# 1_MICROCONTROLADOR.net
KiCad netlist of a schematic drawn in Altium Designer
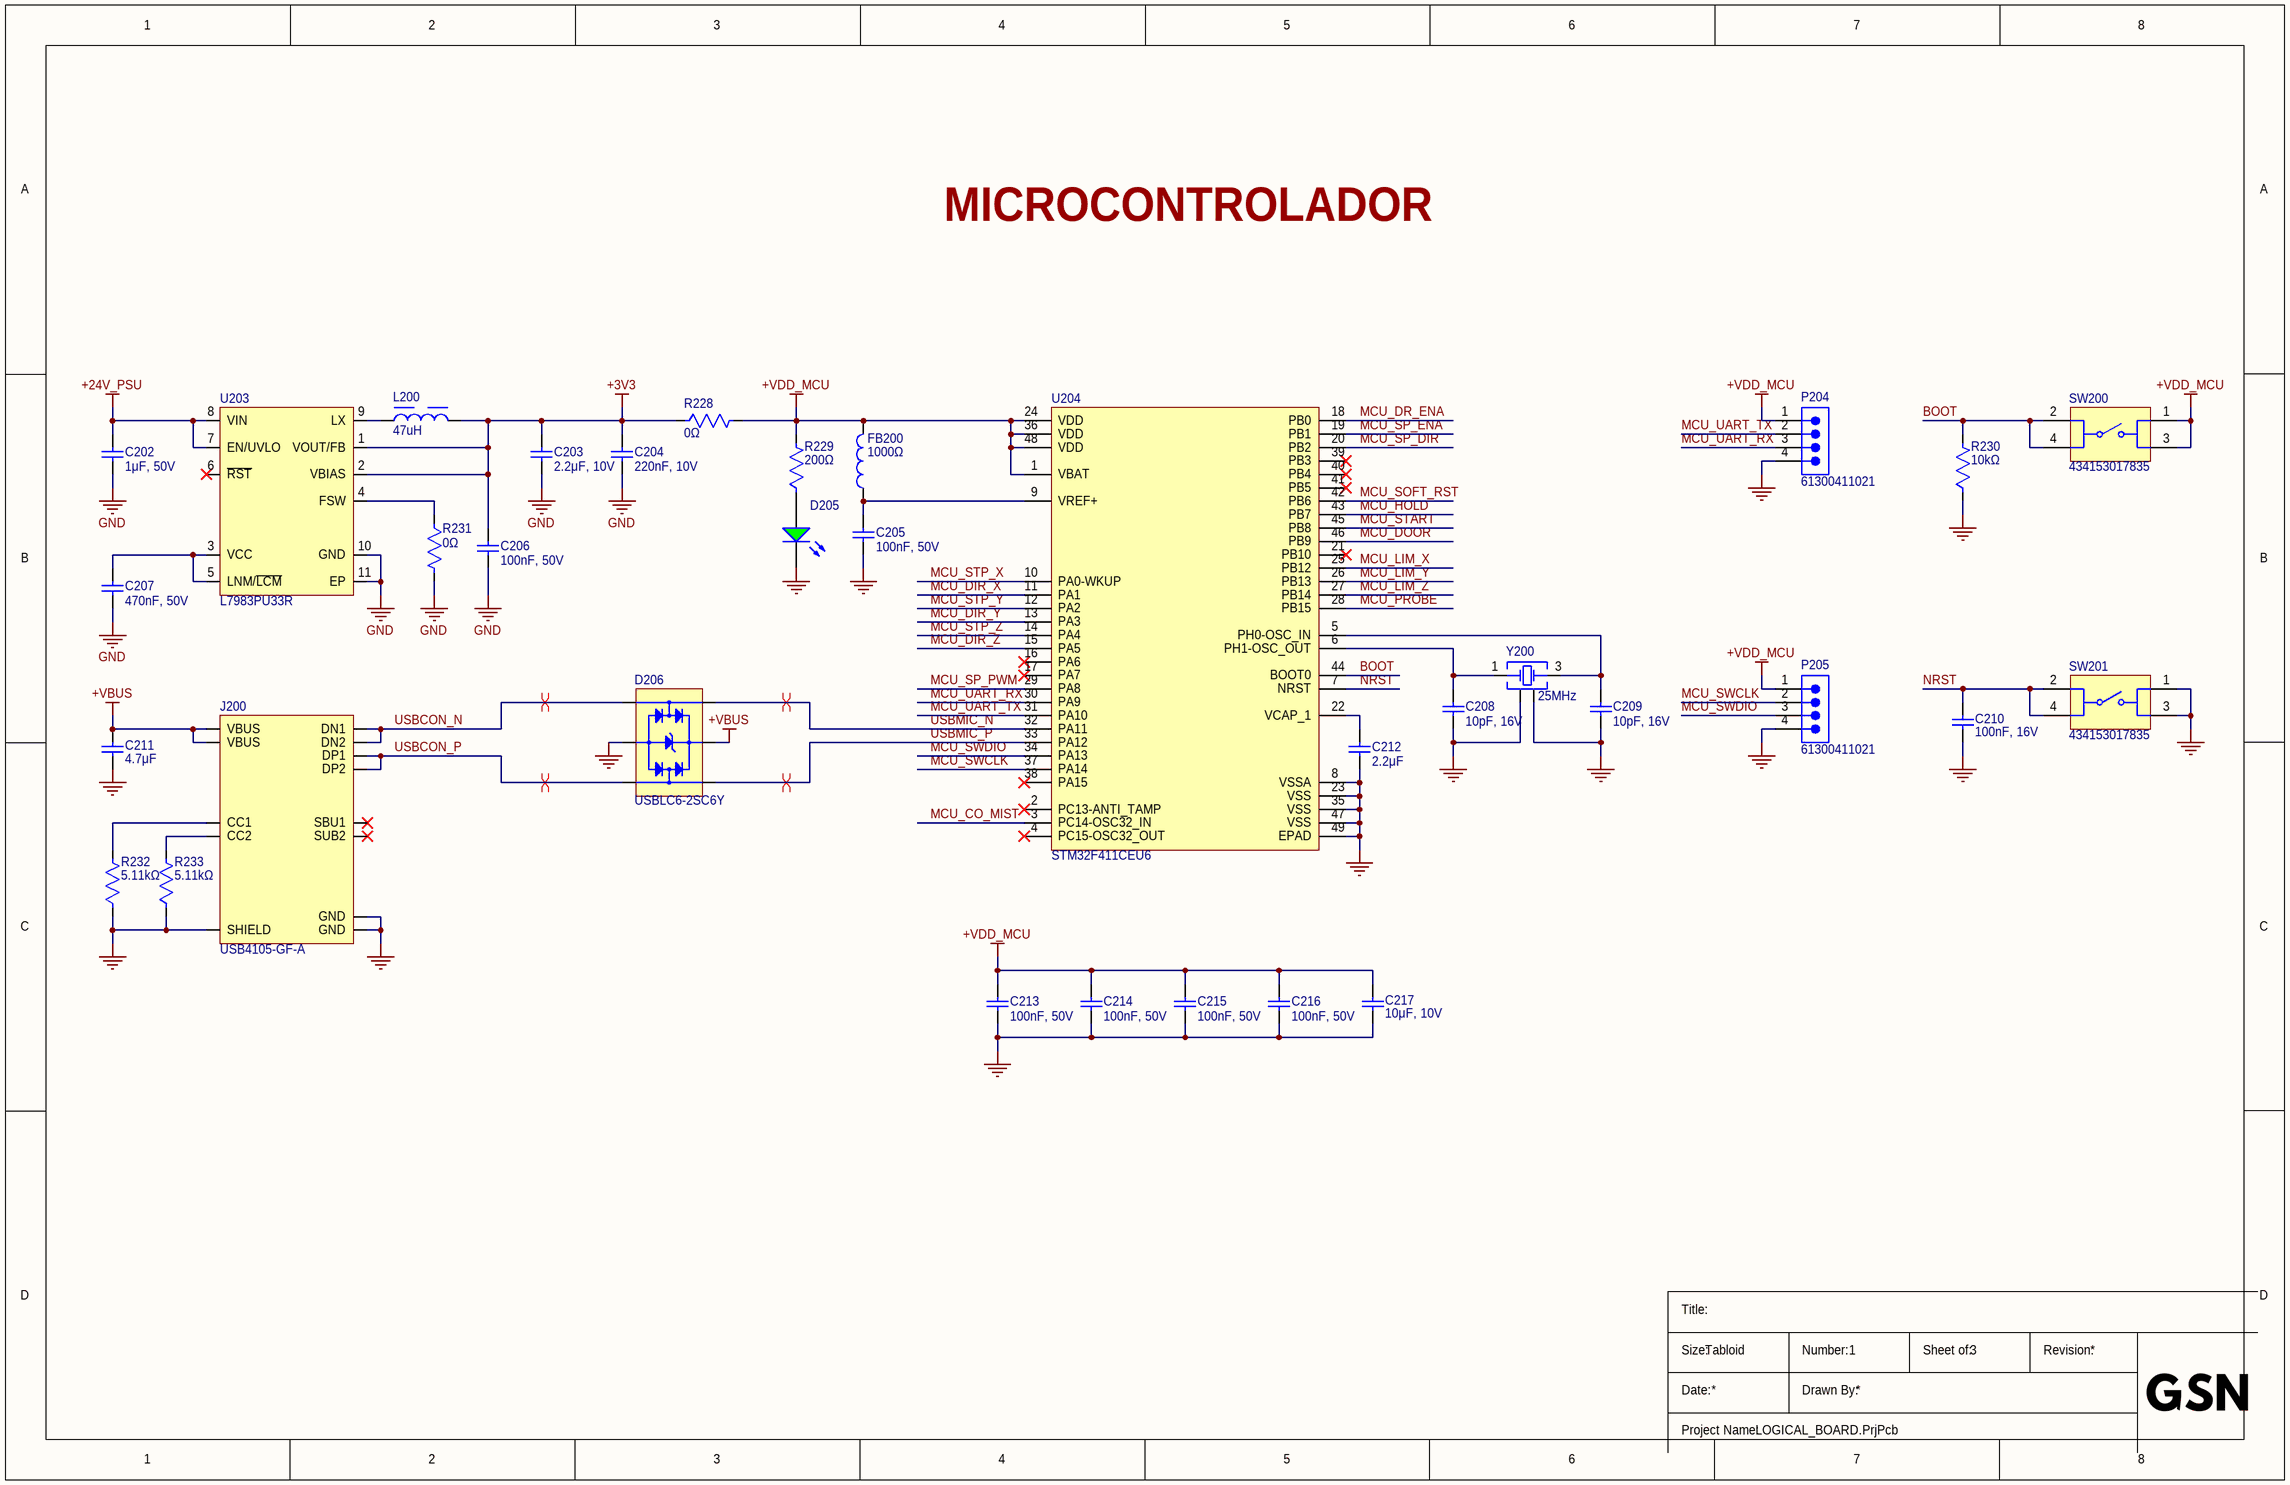
[diagram p0: 1_MICROCONTROLADOR.SchDoc]

(export (version "E")
  (design (tool "Eeschema 10.0.6"))
  (components
    (comp (ref "C202")
      (value "1μF, 50V")
      (footprint "WCAP-CSGP_0805_L2W1.25H1.25")
      (description "WCAP-CSGP Multilayer Ceramic Chip Capacitor, General Purpose, size 0805, 1μF, 50V")
      (fields
        (field (name "MANUFACTURER PART NUMBER") "885012207103R")
        (field (name "MANUFACTURER") "Wurth Elektronik")
      )
      (libsource (lib "WE - Passive Components") (part "Capacitor_Non-Polarized"))
    )
    (comp (ref "C203")
      (value "2.2μF, 10V")
      (footprint "WCAP-CSGP_0603_L1.6W0.8H0.8_Wave")
      (description "WCAP-CSGP Multilayer Ceramic Chip Capacitor, General Purpose, size 0603, 2.2μF, 10V")
      (fields
        (field (name "MANUFACTURER PART NUMBER") "885012206027")
        (field (name "MANUFACTURER") "Wurth Elektronik")
      )
      (libsource (lib "WE - Passive Components") (part "Capacitor_Non-Polarized"))
    )
    (comp (ref "C204")
      (value "220nF, 10V")
      (footprint "WCAP-CSGP_0603_L1.6W0.8H0.8_Wave")
      (description "WCAP-CSGP Multilayer Ceramic Chip Capacitor, General Purpose, size 0603, 220nF, 10V")
      (fields
        (field (name "MANUFACTURER PART NUMBER") "885012206022")
        (field (name "MANUFACTURER") "Wurth Elektronik")
      )
      (libsource (lib "WE - Passive Components") (part "Capacitor_Non-Polarized"))
    )
    (comp (ref "C205")
      (value "100nF, 50V")
      (footprint "WCAP-CSGP_0603_L1.6W0.8H0.8_Wave")
      (description "WCAP-CSGP Multilayer Ceramic Chip Capacitor, General Purpose, size 0603, 100nF, 50V")
      (fields
        (field (name "MANUFACTURER PART NUMBER") "885012206095")
        (field (name "MANUFACTURER") "Wurth Elektronik")
      )
      (libsource (lib "WE - Passive Components") (part "Capacitor_Non-Polarized"))
    )
    (comp (ref "C206")
      (value "100nF, 50V")
      (footprint "WCAP-CSGP_0603_L1.6W0.8H0.8_Wave")
      (description "WCAP-CSGP Multilayer Ceramic Chip Capacitor, General Purpose, size 0603, 100nF, 50V")
      (fields
        (field (name "MANUFACTURER PART NUMBER") "885012206095")
        (field (name "MANUFACTURER") "Wurth Elektronik")
      )
      (libsource (lib "WE - Passive Components") (part "Capacitor_Non-Polarized"))
    )
    (comp (ref "C207")
      (value "470nF, 50V")
      (footprint "WCAP-CSGP_0805_L2W1.25H1.25")
      (description "WCAP-CSGP Multilayer Ceramic Chip Capacitor, General Purpose, size 0805, 470nF, 50V")
      (fields
        (field (name "MANUFACTURER PART NUMBER") "885012207102")
        (field (name "MANUFACTURER") "Wurth Elektronik")
      )
      (libsource (lib "WE - Passive Components") (part "Capacitor_Non-Polarized"))
    )
    (comp (ref "C208")
      (value "10pF, 16V")
      (footprint "WCAP-CSGP_0603_L1.6W0.8H0.8_Wave")
      (description "WCAP-CSGP Multilayer Ceramic Chip Capacitor, General Purpose, size 0603, 10pF, 16V")
      (fields
        (field (name "MANUFACTURER PART NUMBER") "885012006017")
        (field (name "MANUFACTURER") "Wurth Elektronik")
      )
      (libsource (lib "WE - Passive Components") (part "Capacitor_Non-Polarized"))
    )
    (comp (ref "C209")
      (value "10pF, 16V")
      (footprint "WCAP-CSGP_0603_L1.6W0.8H0.8_Wave")
      (description "WCAP-CSGP Multilayer Ceramic Chip Capacitor, General Purpose, size 0603, 10pF, 16V")
      (fields
        (field (name "MANUFACTURER PART NUMBER") "885012006017")
        (field (name "MANUFACTURER") "Wurth Elektronik")
      )
      (libsource (lib "WE - Passive Components") (part "Capacitor_Non-Polarized"))
    )
    (comp (ref "C210")
      (value "100nF, 16V")
      (footprint "WCAP-CSGP_0603_L1.6W0.8H0.8_Wave")
      (description "WCAP-CSGP Multilayer Ceramic Chip Capacitor, General Purpose, size 0603, 100nF, 16V")
      (fields
        (field (name "MANUFACTURER PART NUMBER") "885012206046")
        (field (name "MANUFACTURER") "Wurth Elektronik")
      )
      (libsource (lib "WE - Passive Components") (part "Capacitor_Non-Polarized"))
    )
    (comp (ref "C211")
      (value "4.7μF")
      (footprint "WCAP-CSGP_0805_L2W1.25H1.25")
      (description "WCAP-CSGP Multilayer Ceramic Chip Capacitor, General Purpose, size 0805, 4.7μF, 16V")
      (fields
        (field (name "MANUFACTURER PART NUMBER") "885012207053")
        (field (name "MANUFACTURER") "Wurth Elektronik")
      )
      (libsource (lib "WE - Passive Components") (part "Capacitor_Non-Polarized"))
    )
    (comp (ref "C212")
      (value "2.2μF")
      (footprint "WCAP-CSGP_0603_L1.6W0.8H0.8_Wave")
      (description "WCAP-CSGP Multilayer Ceramic Chip Capacitor, General Purpose, size 0603, 2.2μF, 6.3V")
      (fields
        (field (name "MANUFACTURER PART NUMBER") "885012106004")
        (field (name "MANUFACTURER") "Wurth Elektronik")
      )
      (libsource (lib "WE - Passive Components") (part "Capacitor_Non-Polarized"))
    )
    (comp (ref "C213")
      (value "100nF, 50V")
      (footprint "WCAP-CSGP_0603_L1.6W0.8H0.8_Wave")
      (description "WCAP-CSGP Multilayer Ceramic Chip Capacitor, General Purpose, size 0603, 100nF, 50V")
      (fields
        (field (name "MANUFACTURER PART NUMBER") "885012206095")
        (field (name "MANUFACTURER") "Wurth Elektronik")
      )
      (libsource (lib "WE - Passive Components") (part "Capacitor_Non-Polarized"))
    )
    (comp (ref "C214")
      (value "100nF, 50V")
      (footprint "WCAP-CSGP_0603_L1.6W0.8H0.8_Wave")
      (description "WCAP-CSGP Multilayer Ceramic Chip Capacitor, General Purpose, size 0603, 100nF, 50V")
      (fields
        (field (name "MANUFACTURER PART NUMBER") "885012206095")
        (field (name "MANUFACTURER") "Wurth Elektronik")
      )
      (libsource (lib "WE - Passive Components") (part "Capacitor_Non-Polarized"))
    )
    (comp (ref "C215")
      (value "100nF, 50V")
      (footprint "WCAP-CSGP_0603_L1.6W0.8H0.8_Wave")
      (description "WCAP-CSGP Multilayer Ceramic Chip Capacitor, General Purpose, size 0603, 100nF, 50V")
      (fields
        (field (name "MANUFACTURER PART NUMBER") "885012206095")
        (field (name "MANUFACTURER") "Wurth Elektronik")
      )
      (libsource (lib "WE - Passive Components") (part "Capacitor_Non-Polarized"))
    )
    (comp (ref "C216")
      (value "100nF, 50V")
      (footprint "WCAP-CSGP_0603_L1.6W0.8H0.8_Wave")
      (description "WCAP-CSGP Multilayer Ceramic Chip Capacitor, General Purpose, size 0603, 100nF, 50V")
      (fields
        (field (name "MANUFACTURER PART NUMBER") "885012206095")
        (field (name "MANUFACTURER") "Wurth Elektronik")
      )
      (libsource (lib "WE - Passive Components") (part "Capacitor_Non-Polarized"))
    )
    (comp (ref "C217")
      (value "10μF, 10V")
      (footprint "WCAP-CSGP_0805_L2W1.25H1.25")
      (description "WCAP-CSGP Multilayer Ceramic Chip Capacitor, General Purpose, size 0805, 10μF, 10V")
      (fields
        (field (name "MANUFACTURER PART NUMBER") "885012207026")
        (field (name "MANUFACTURER") "Wurth Elektronik")
      )
      (libsource (lib "WE - Passive Components") (part "Capacitor_Non-Polarized"))
    )
    (comp (ref "D205")
      (value "Bright Green, 2V, 140deg")
      (footprint "WL-SMCW_0603_150060xx75000")
      (description "WL-SMCW Mono-color Chip LED Waterclear, SMT, size 0603, Bright Green, 2V, 140°")
      (fields
        (field (name "MANUFACTURER PART NUMBER") "150060VS75000")
        (field (name "MANUFACTURER") "Wurth Elektronik")
      )
      (libsource (lib "WE - Optoelectronic Components") (part "LED_Green_2A-1K"))
    )
    (comp (ref "D206")
      (value "USBLC6-2SC6Y")
      (footprint "SOT-23-6")
      (description "TVS DIODE 5.25VWM 17VC SOT23-6")
      (fields (field (name "MANUFACTURER") "STMicroelectronics"))
      (libsource (lib "TVS-Diodes") (part "USBLC6-2SC6Y"))
    )
    (comp (ref "FB200")
      (value "1000Ω")
      (footprint "WE-CBF_0603_L1.6W0.8H0.8_HS_WB")
      (description "WE-CBF SMT EMI Suppression Ferrite Bead, size 0603, 1000Ω, 0.65A")
      (fields
        (field (name "MANUFACTURER PART NUMBER") "74279266")
        (field (name "MANUFACTURER") "Wurth Elektronik")
      )
      (libsource (lib "WE - Passive Components") (part "Ferrite"))
    )
    (comp (ref "J200")
      (value "USB4105-GF-A")
      (footprint "USB4105-GF-A")
      (description "CONN RCP USB2.0 TYP C 16P SMD RA")
      (fields (field (name "MANUFACTURER") "Global Connector Technology"))
      (libsource (lib "Connectors") (part "USB4105-GF-A"))
    )
    (comp (ref "L200")
      (value "47uH")
      (footprint "WE-MAIA_3015")
      (description "WE-MAIA SMT Power Inductor, size 3015, 47uH, 0.5A, 2300mohm")
      (fields
        (field (name "MANUFACTURER PART NUMBER") "78438335470")
        (field (name "MANUFACTURER") "Wurth Elektronik")
      )
      (libsource (lib "WE - Passive Components") (part "Inductor - 3"))
    )
    (comp (ref "P204")
      (value "61300411021")
      (footprint "61300411021")
      (description "WR-PHD Pin Header, THT, Angled, pitch 2.54mm, 1 Row, 4P")
      (fields (field (name "MANUFACTURER") "Wurth Elektronik"))
      (libsource (lib "WE - Electromechanical Components") (part "Header_Male_1R_04P"))
    )
    (comp (ref "P205")
      (value "61300411021")
      (footprint "61300411021")
      (description "WR-PHD Pin Header, THT, Angled, pitch 2.54mm, 1 Row, 4P")
      (fields (field (name "MANUFACTURER") "Wurth Elektronik"))
      (libsource (lib "WE - Electromechanical Components") (part "Header_Male_1R_04P"))
    )
    (comp (ref "R228")
      (value "0Ω")
      (footprint "0805-WAVE")
      (description "RES 0 OHM 1% 1/8W 0805")
      (fields
        (field (name "MANUFACTURER") "Yageo Group")
        (field (name "MANUFACTURER PART NUMBER") "RC0805FR-070RL")
      )
      (libsource (lib "Resistors-0805-E96-Yageo") (part "RC0805FR-070RL"))
    )
    (comp (ref "R229")
      (value "200Ω")
      (footprint "0603-WAVE")
      (description "RES 200 OHM 1% 1/10W 0603")
      (fields
        (field (name "MANUFACTURER PART NUMBER") "RC0603FR-07200RL")
        (field (name "MANUFACTURER") "Yageo Group")
      )
      (libsource (lib "Resistors-0603-E96-Yageo") (part "RC0603FR-07200RL"))
    )
    (comp (ref "R230")
      (value "10kΩ")
      (footprint "0603-WAVE")
      (description "RES 10K OHM 1% 1/10W 0603")
      (fields
        (field (name "MANUFACTURER PART NUMBER") "RC0603FR-0710KL")
        (field (name "MANUFACTURER") "Yageo Group")
      )
      (libsource (lib "Resistors-0603-E96-Yageo") (part "RC0603FR-0710KL"))
    )
    (comp (ref "R231")
      (value "0Ω")
      (footprint "0603-WAVE")
      (description "RES 0 OHM 1% 1/10W 0603")
      (fields
        (field (name "MANUFACTURER PART NUMBER") "RC0603FR-070RL")
        (field (name "MANUFACTURER") "Yageo Group")
      )
      (libsource (lib "Resistors-0603-E96-Yageo") (part "RC0603FR-070RL"))
    )
    (comp (ref "R232")
      (value "5.11kΩ")
      (footprint "0603-WAVE")
      (description "RES 5.11K OHM 1% 1/10W 0603")
      (fields
        (field (name "MANUFACTURER PART NUMBER") "RC0603FR-075K11L")
        (field (name "MANUFACTURER") "Yageo Group")
      )
      (libsource (lib "Resistors-0603-E96-Yageo") (part "RC0603FR-075K11L"))
    )
    (comp (ref "R233")
      (value "5.11kΩ")
      (footprint "0603-WAVE")
      (description "RES 5.11K OHM 1% 1/10W 0603")
      (fields
        (field (name "MANUFACTURER PART NUMBER") "RC0603FR-075K11L")
        (field (name "MANUFACTURER") "Yageo Group")
      )
      (libsource (lib "Resistors-0603-E96-Yageo") (part "RC0603FR-075K11L"))
    )
    (comp (ref "SW200")
      (value "434153017835")
      (footprint "434153017835")
      (description "WS-TASV J-Bend SMT Tact Switch, 3.5mm x 2.9mm x 1.7mm, SPST-NO, 350gf, 12V, 50mA")
      (fields (field (name "MANUFACTURER") "Wurth Elektronik"))
      (libsource (lib "WE - Electromechanical Components") (part "SPST-NO_4P_24-13"))
    )
    (comp (ref "SW201")
      (value "434153017835")
      (footprint "434153017835")
      (description "WS-TASV J-Bend SMT Tact Switch, 3.5mm x 2.9mm x 1.7mm, SPST-NO, 350gf, 12V, 50mA")
      (fields (field (name "MANUFACTURER") "Wurth Elektronik"))
      (libsource (lib "WE - Electromechanical Components") (part "SPST-NO_4P_24-13"))
    )
    (comp (ref "U203")
      (value "L7983PU33R")
      (footprint "10-WFDFN-EP")
      (description "IC REG BUCK 3.3V 300MA 10DFN")
      (fields (field (name "MANUFACTURER") "STMicroelectronics"))
      (libsource (lib "Voltage-Regulators") (part "L7983PU33R"))
    )
    (comp (ref "U204")
      (value "STM32F411CEU6")
      (footprint "UFQFN-48-7X7_EXPOSED_PAD")
      (description "IC MCU 32BIT 512KB FLSH 48UFQFPN")
      (fields (field (name "MANUFACTURER") "STMicroelectronics"))
      (libsource (lib "Microcontrollers") (part "STM32F411CEU6"))
    )
    (comp (ref "Y200")
      (value "25MHz")
      (footprint "WE-XTAL_IQXC-42")
      (description "WE-XTAL Quartz Crystal, IQXC-42, 25MHz, +/-15ppm")
      (fields
        (field (name "MANUFACTURER PART NUMBER") "830069494")
        (field (name "MANUFACTURER") "Wurth Elektronik")
      )
      (libsource (lib "WE - Passive Components") (part "WE-XTAL_IQXC-42"))
    )
  )
  (nets
    (net (code "1") (name "+3V3") (class "Default")
      (node (ref "C203") (pin "2") (pinfunction "2_2") (pintype "passive"))
      (node (ref "C204") (pin "2") (pinfunction "2_2") (pintype "passive"))
      (node (ref "C206") (pin "2") (pinfunction "2_2") (pintype "passive"))
      (node (ref "L200") (pin "2") (pinfunction "2_2") (pintype "passive"))
      (node (ref "R228") (pin "1") (pinfunction "1_1") (pintype "passive"))
      (node (ref "U203") (pin "1") (pinfunction "VOUT/FB_1") (pintype "passive"))
      (node (ref "U203") (pin "2") (pinfunction "VBIAS_2") (pintype "passive"))
    )
    (net (code "2") (name "+24V_PSU") (class "Default")
      (node (ref "C202") (pin "2") (pinfunction "2_2") (pintype "passive"))
      (node (ref "U203") (pin "7") (pinfunction "EN/UVLO_7") (pintype "passive"))
      (node (ref "U203") (pin "8") (pinfunction "VIN_8") (pintype "passive"))
    )
    (net (code "3") (name "+VBUS") (class "Default")
      (node (ref "C211") (pin "2") (pinfunction "2_2") (pintype "passive"))
      (node (ref "D206") (pin "5") (pinfunction "VBUS_5") (pintype "passive"))
      (node (ref "J200") (pin "A4_B9") (pinfunction "VBUS_A4_B9") (pintype "passive"))
      (node (ref "J200") (pin "B4_A9") (pinfunction "VBUS_B4_A9") (pintype "passive"))
    )
    (net (code "4") (name "+VDD_MCU") (class "Default")
      (node (ref "C213") (pin "2") (pinfunction "2_2") (pintype "passive"))
      (node (ref "C214") (pin "2") (pinfunction "2_2") (pintype "passive"))
      (node (ref "C215") (pin "2") (pinfunction "2_2") (pintype "passive"))
      (node (ref "C216") (pin "2") (pinfunction "2_2") (pintype "passive"))
      (node (ref "C217") (pin "2") (pinfunction "2_2") (pintype "passive"))
      (node (ref "FB200") (pin "2") (pinfunction "2_2") (pintype "passive"))
      (node (ref "P204") (pin "1") (pinfunction "1_1") (pintype "passive"))
      (node (ref "P205") (pin "1") (pinfunction "1_1") (pintype "passive"))
      (node (ref "R228") (pin "2") (pinfunction "2_2") (pintype "passive"))
      (node (ref "R229") (pin "2") (pinfunction "2_2") (pintype "passive"))
      (node (ref "SW200") (pin "1") (pinfunction "1_1") (pintype "passive"))
      (node (ref "SW200") (pin "3") (pinfunction "3_3") (pintype "passive"))
      (node (ref "U204") (pin "1") (pinfunction "VBAT_1") (pintype "passive"))
      (node (ref "U204") (pin "24") (pinfunction "VDD_24") (pintype "passive"))
      (node (ref "U204") (pin "36") (pinfunction "VDD_36") (pintype "passive"))
      (node (ref "U204") (pin "48") (pinfunction "VDD_48") (pintype "passive"))
    )
    (net (code "5") (name "/BOOT") (class "Default")
      (node (ref "R230") (pin "2") (pinfunction "2_2") (pintype "passive"))
      (node (ref "SW200") (pin "2") (pinfunction "2_2") (pintype "passive"))
      (node (ref "SW200") (pin "4") (pinfunction "4_4") (pintype "passive"))
      (node (ref "U204") (pin "44") (pinfunction "BOOT0_44") (pintype "passive"))
    )
    (net (code "6") (name "/MCU_CO_MIST") (class "Default")
      (node (ref "U204") (pin "3") (pinfunction "PC14-OSC32_IN_3") (pintype "passive"))
    )
    (net (code "7") (name "/MCU_DIR_X") (class "Default")
      (node (ref "U204") (pin "11") (pinfunction "PA1_11") (pintype "passive"))
    )
    (net (code "8") (name "/MCU_DIR_Y") (class "Default")
      (node (ref "U204") (pin "13") (pinfunction "PA3_13") (pintype "passive"))
    )
    (net (code "9") (name "/MCU_DIR_Z") (class "Default")
      (node (ref "U204") (pin "15") (pinfunction "PA5_15") (pintype "passive"))
    )
    (net (code "10") (name "/MCU_DOOR") (class "Default")
      (node (ref "U204") (pin "46") (pinfunction "PB9_46") (pintype "passive"))
    )
    (net (code "11") (name "/MCU_DR_ENA") (class "Default")
      (node (ref "U204") (pin "18") (pinfunction "PB0_18") (pintype "passive"))
    )
    (net (code "12") (name "/MCU_HOLD") (class "Default")
      (node (ref "U204") (pin "43") (pinfunction "PB7_43") (pintype "passive"))
    )
    (net (code "13") (name "/MCU_LIM_X") (class "Default")
      (node (ref "U204") (pin "25") (pinfunction "PB12_25") (pintype "passive"))
    )
    (net (code "14") (name "/MCU_LIM_Y") (class "Default")
      (node (ref "U204") (pin "26") (pinfunction "PB13_26") (pintype "passive"))
    )
    (net (code "15") (name "/MCU_LIM_Z") (class "Default")
      (node (ref "U204") (pin "27") (pinfunction "PB14_27") (pintype "passive"))
    )
    (net (code "16") (name "/MCU_PROBE") (class "Default")
      (node (ref "U204") (pin "28") (pinfunction "PB15_28") (pintype "passive"))
    )
    (net (code "17") (name "/MCU_SOFT_RST") (class "Default")
      (node (ref "U204") (pin "42") (pinfunction "PB6_42") (pintype "passive"))
    )
    (net (code "18") (name "/MCU_SP_DIR") (class "Default")
      (node (ref "U204") (pin "20") (pinfunction "PB2_20") (pintype "passive"))
    )
    (net (code "19") (name "/MCU_SP_ENA") (class "Default")
      (node (ref "U204") (pin "19") (pinfunction "PB1_19") (pintype "passive"))
    )
    (net (code "20") (name "/MCU_SP_PWM") (class "Default")
      (node (ref "U204") (pin "29") (pinfunction "PA8_29") (pintype "passive"))
    )
    (net (code "21") (name "/MCU_START") (class "Default")
      (node (ref "U204") (pin "45") (pinfunction "PB8_45") (pintype "passive"))
    )
    (net (code "22") (name "/MCU_STP_X") (class "Default")
      (node (ref "U204") (pin "10") (pinfunction "PA0-WKUP_10") (pintype "passive"))
    )
    (net (code "23") (name "/MCU_STP_Y") (class "Default")
      (node (ref "U204") (pin "12") (pinfunction "PA2_12") (pintype "passive"))
    )
    (net (code "24") (name "/MCU_STP_Z") (class "Default")
      (node (ref "U204") (pin "14") (pinfunction "PA4_14") (pintype "passive"))
    )
    (net (code "25") (name "/MCU_SWCLK") (class "Default")
      (node (ref "P205") (pin "2") (pinfunction "2_2") (pintype "passive"))
      (node (ref "U204") (pin "37") (pinfunction "PA14_37") (pintype "passive"))
    )
    (net (code "26") (name "/MCU_SWDIO") (class "Default")
      (node (ref "P205") (pin "3") (pinfunction "3_3") (pintype "passive"))
      (node (ref "U204") (pin "34") (pinfunction "PA13_34") (pintype "passive"))
    )
    (net (code "27") (name "/MCU_UART_RX") (class "Default")
      (node (ref "P204") (pin "3") (pinfunction "3_3") (pintype "passive"))
      (node (ref "U204") (pin "30") (pinfunction "PA9_30") (pintype "passive"))
    )
    (net (code "28") (name "/MCU_UART_TX") (class "Default")
      (node (ref "P204") (pin "2") (pinfunction "2_2") (pintype "passive"))
      (node (ref "U204") (pin "31") (pinfunction "PA10_31") (pintype "passive"))
    )
    (net (code "29") (name "/NRST") (class "Default")
      (node (ref "C210") (pin "2") (pinfunction "2_2") (pintype "passive"))
      (node (ref "SW201") (pin "2") (pinfunction "2_2") (pintype "passive"))
      (node (ref "SW201") (pin "4") (pinfunction "4_4") (pintype "passive"))
      (node (ref "U204") (pin "7") (pinfunction "NRST_7") (pintype "passive"))
    )
    (net (code "30") (name "/USBCON_N") (class "Default")
      (node (ref "D206") (pin "1") (pinfunction "IO1_1") (pintype "passive"))
      (node (ref "J200") (pin "A7") (pinfunction "DN1_A7") (pintype "passive"))
      (node (ref "J200") (pin "B7") (pinfunction "DN2_B7") (pintype "passive"))
    )
    (net (code "31") (name "/USBCON_P") (class "Default")
      (node (ref "D206") (pin "3") (pinfunction "IO2_3") (pintype "passive"))
      (node (ref "J200") (pin "A6") (pinfunction "DP1_A6") (pintype "passive"))
      (node (ref "J200") (pin "B6") (pinfunction "DP2_B6") (pintype "passive"))
    )
    (net (code "32") (name "/USBMIC_N") (class "Default")
      (node (ref "D206") (pin "6") (pinfunction "IO1_6") (pintype "passive"))
      (node (ref "U204") (pin "32") (pinfunction "PA11_32") (pintype "passive"))
    )
    (net (code "33") (name "/USBMIC_P") (class "Default")
      (node (ref "D206") (pin "4") (pinfunction "IO2_4") (pintype "passive"))
      (node (ref "U204") (pin "33") (pinfunction "PA12_33") (pintype "passive"))
    )
    (net (code "34") (name "GND") (class "Default")
      (node (ref "C202") (pin "1") (pinfunction "1_1") (pintype "passive"))
      (node (ref "C203") (pin "1") (pinfunction "1_1") (pintype "passive"))
      (node (ref "C204") (pin "1") (pinfunction "1_1") (pintype "passive"))
      (node (ref "C205") (pin "1") (pinfunction "1_1") (pintype "passive"))
      (node (ref "C206") (pin "1") (pinfunction "1_1") (pintype "passive"))
      (node (ref "C207") (pin "1") (pinfunction "1_1") (pintype "passive"))
      (node (ref "C208") (pin "1") (pinfunction "1_1") (pintype "passive"))
      (node (ref "C209") (pin "1") (pinfunction "1_1") (pintype "passive"))
      (node (ref "C210") (pin "1") (pinfunction "1_1") (pintype "passive"))
      (node (ref "C211") (pin "1") (pinfunction "1_1") (pintype "passive"))
      (node (ref "C212") (pin "1") (pinfunction "1_1") (pintype "passive"))
      (node (ref "C213") (pin "1") (pinfunction "1_1") (pintype "passive"))
      (node (ref "C214") (pin "1") (pinfunction "1_1") (pintype "passive"))
      (node (ref "C215") (pin "1") (pinfunction "1_1") (pintype "passive"))
      (node (ref "C216") (pin "1") (pinfunction "1_1") (pintype "passive"))
      (node (ref "C217") (pin "1") (pinfunction "1_1") (pintype "passive"))
      (node (ref "D205") (pin "1") (pinfunction "K_1") (pintype "passive"))
      (node (ref "D206") (pin "2") (pinfunction "GND_2") (pintype "passive"))
      (node (ref "J200") (pin "A1_B12") (pinfunction "GND_A1_B12") (pintype "power_in"))
      (node (ref "J200") (pin "B1_A12") (pinfunction "GND_B1_A12") (pintype "power_in"))
      (node (ref "J200") (pin "SH") (pinfunction "SHIELD_SH") (pintype "passive"))
      (node (ref "P204") (pin "4") (pinfunction "4_4") (pintype "passive"))
      (node (ref "P205") (pin "4") (pinfunction "4_4") (pintype "passive"))
      (node (ref "R230") (pin "1") (pinfunction "1_1") (pintype "passive"))
      (node (ref "R231") (pin "2") (pinfunction "2_2") (pintype "passive"))
      (node (ref "R232") (pin "1") (pinfunction "1_1") (pintype "passive"))
      (node (ref "R233") (pin "1") (pinfunction "1_1") (pintype "passive"))
      (node (ref "SW201") (pin "1") (pinfunction "1_1") (pintype "passive"))
      (node (ref "SW201") (pin "3") (pinfunction "3_3") (pintype "passive"))
      (node (ref "U203") (pin "10") (pinfunction "GND_10") (pintype "passive"))
      (node (ref "U203") (pin "11") (pinfunction "EP_11") (pintype "passive"))
      (node (ref "U204") (pin "23") (pinfunction "VSS_23") (pintype "passive"))
      (node (ref "U204") (pin "35") (pinfunction "VSS_35") (pintype "passive"))
      (node (ref "U204") (pin "47") (pinfunction "VSS_47") (pintype "passive"))
      (node (ref "U204") (pin "49") (pinfunction "EPAD_49") (pintype "passive"))
      (node (ref "U204") (pin "8") (pinfunction "VSSA_8") (pintype "passive"))
      (node (ref "Y200") (pin "2") (pinfunction "GND_&_Lid_2") (pintype "passive"))
      (node (ref "Y200") (pin "4") (pinfunction "GND_&_Lid_4") (pintype "passive"))
    )
    (net (code "35") (name "Net-(D205-A)") (class "Default")
      (node (ref "D205") (pin "2") (pinfunction "A_2") (pintype "passive"))
      (node (ref "R229") (pin "1") (pinfunction "1_1") (pintype "passive"))
    )
    (net (code "36") (name "Net-(J200-CC1)") (class "Default")
      (node (ref "J200") (pin "A5") (pinfunction "CC1_A5") (pintype "passive"))
      (node (ref "R232") (pin "2") (pinfunction "2_2") (pintype "passive"))
    )
    (net (code "37") (name "Net-(J200-CC2)") (class "Default")
      (node (ref "J200") (pin "B5") (pinfunction "CC2_B5") (pintype "passive"))
      (node (ref "R233") (pin "2") (pinfunction "2_2") (pintype "passive"))
    )
    (net (code "38") (name "Net-(U203-FSW)") (class "Default")
      (node (ref "R231") (pin "1") (pinfunction "1_1") (pintype "passive"))
      (node (ref "U203") (pin "4") (pinfunction "FSW_4") (pintype "passive"))
    )
    (net (code "39") (name "Net-(U203-LNM{slash}~{LCM})") (class "Default")
      (node (ref "C207") (pin "2") (pinfunction "2_2") (pintype "passive"))
      (node (ref "U203") (pin "3") (pinfunction "VCC_3") (pintype "passive"))
      (node (ref "U203") (pin "5") (pinfunction "LNM/~{LCM}_5") (pintype "passive"))
    )
    (net (code "40") (name "Net-(U203-LX)") (class "Default")
      (node (ref "L200") (pin "1") (pinfunction "1_1") (pintype "passive"))
      (node (ref "U203") (pin "9") (pinfunction "LX_9") (pintype "passive"))
    )
    (net (code "41") (name "Net-(U204-PH0-OSC_IN)") (class "Default")
      (node (ref "C209") (pin "2") (pinfunction "2_2") (pintype "passive"))
      (node (ref "U204") (pin "5") (pinfunction "PH0-OSC_IN_5") (pintype "passive"))
      (node (ref "Y200") (pin "3") (pinfunction "Crystal_3") (pintype "passive"))
    )
    (net (code "42") (name "Net-(U204-PH1-OSC_OUT)") (class "Default")
      (node (ref "C208") (pin "2") (pinfunction "2_2") (pintype "passive"))
      (node (ref "U204") (pin "6") (pinfunction "PH1-OSC_OUT_6") (pintype "passive"))
      (node (ref "Y200") (pin "1") (pinfunction "Crystal_1") (pintype "passive"))
    )
    (net (code "43") (name "Net-(U204-VCAP_1)") (class "Default")
      (node (ref "C212") (pin "2") (pinfunction "2_2") (pintype "passive"))
      (node (ref "U204") (pin "22") (pinfunction "VCAP_1_22") (pintype "passive"))
    )
    (net (code "44") (name "Net-(U204-VREF+)") (class "Default")
      (node (ref "C205") (pin "2") (pinfunction "2_2") (pintype "passive"))
      (node (ref "FB200") (pin "1") (pinfunction "1_1") (pintype "passive"))
      (node (ref "U204") (pin "9") (pinfunction "VREF+_9") (pintype "passive"))
    )
    (net (code "45") (name "unconnected-(J200-SBU1-PadA8)") (class "Default")
      (node (ref "J200") (pin "A8") (pinfunction "SBU1_A8") (pintype "passive+no_connect"))
    )
    (net (code "46") (name "unconnected-(J200-SUB2-PadB8)") (class "Default")
      (node (ref "J200") (pin "B8") (pinfunction "SUB2_B8") (pintype "passive+no_connect"))
    )
    (net (code "47") (name "unconnected-(U203-~{RST}-Pad6)") (class "Default")
      (node (ref "U203") (pin "6") (pinfunction "~{RST}_6") (pintype "passive+no_connect"))
    )
    (net (code "48") (name "unconnected-(U204-PA6-Pad16)") (class "Default")
      (node (ref "U204") (pin "16") (pinfunction "PA6_16") (pintype "passive+no_connect"))
    )
    (net (code "49") (name "unconnected-(U204-PA7-Pad17)") (class "Default")
      (node (ref "U204") (pin "17") (pinfunction "PA7_17") (pintype "passive+no_connect"))
    )
    (net (code "50") (name "unconnected-(U204-PA15-Pad38)") (class "Default")
      (node (ref "U204") (pin "38") (pinfunction "PA15_38") (pintype "passive+no_connect"))
    )
    (net (code "51") (name "unconnected-(U204-PB3-Pad39)") (class "Default")
      (node (ref "U204") (pin "39") (pinfunction "PB3_39") (pintype "passive+no_connect"))
    )
    (net (code "52") (name "unconnected-(U204-PB4-Pad40)") (class "Default")
      (node (ref "U204") (pin "40") (pinfunction "PB4_40") (pintype "passive+no_connect"))
    )
    (net (code "53") (name "unconnected-(U204-PB5-Pad41)") (class "Default")
      (node (ref "U204") (pin "41") (pinfunction "PB5_41") (pintype "passive+no_connect"))
    )
    (net (code "54") (name "unconnected-(U204-PB10-Pad21)") (class "Default")
      (node (ref "U204") (pin "21") (pinfunction "PB10_21") (pintype "passive+no_connect"))
    )
    (net (code "55") (name "unconnected-(U204-PC13-ANTI_TAMP-Pad2)") (class "Default")
      (node (ref "U204") (pin "2") (pinfunction "PC13-ANTI_TAMP_2") (pintype "passive+no_connect"))
    )
    (net (code "56") (name "unconnected-(U204-PC15-OSC32_OUT-Pad4)") (class "Default")
      (node (ref "U204") (pin "4") (pinfunction "PC15-OSC32_OUT_4") (pintype "passive+no_connect"))
    )
  )
)
